# ArduinoUno.net
KiCad netlist of a schematic drawn in Altium Designer
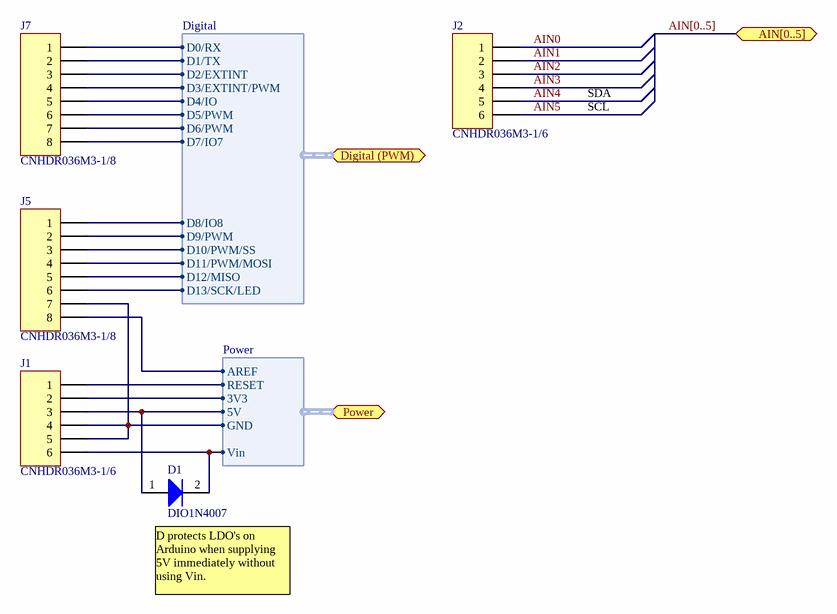
[diagram p0: ArduinoUno.SchDoc]

(export (version "E")
  (design (tool "Eeschema 10.0.6"))
  (components
    (comp (ref "D1")
      (value "DIO1N4007")
      (footprint "DO-41")
      (description "1 Amp General Purpose Rectifier")
      (libsource (lib "Testing") (part "D_DIODE"))
    )
    (comp (ref "J1")
      (value "CNHDR036M3-1/6")
      (footprint "J_HDR1X6")
      (libsource (lib "Testing") (part "J_6P"))
    )
    (comp (ref "J2")
      (value "CNHDR036M3-1/6")
      (footprint "J_HDR1X6")
      (libsource (lib "Testing") (part "J_6P"))
    )
    (comp (ref "J5")
      (value "CNHDR036M3-1/8")
      (footprint "J_HDR1X8")
      (libsource (lib "Testing") (part "J_8P"))
    )
    (comp (ref "J7")
      (value "CNHDR036M3-1/8")
      (footprint "J_HDR1X8")
      (libsource (lib "Testing") (part "J_8P"))
    )
  )
  (nets
    (net (code "3") (name "/3V3") (class "Default")
      (node (ref "J1") (pin "2") (pinfunction "2_2") (pintype "passive"))
    )
    (net (code "4") (name "/5V") (class "Default")
      (node (ref "D1") (pin "1") (pinfunction "A_1") (pintype "passive"))
      (node (ref "J1") (pin "3") (pinfunction "3_3") (pintype "passive"))
    )
    (net (code "5") (name "/AIN0") (class "Default")
      (node (ref "J2") (pin "1") (pinfunction "1_1") (pintype "passive"))
    )
    (net (code "6") (name "/AIN1") (class "Default")
      (node (ref "J2") (pin "2") (pinfunction "2_2") (pintype "passive"))
    )
    (net (code "7") (name "/AIN2") (class "Default")
      (node (ref "J2") (pin "3") (pinfunction "3_3") (pintype "passive"))
    )
    (net (code "8") (name "/AIN3") (class "Default")
      (node (ref "J2") (pin "4") (pinfunction "4_4") (pintype "passive"))
    )
    (net (code "9") (name "/AIN4") (class "Default")
      (node (ref "J2") (pin "5") (pinfunction "5_5") (pintype "passive"))
    )
    (net (code "10") (name "/AIN5") (class "Default")
      (node (ref "J2") (pin "6") (pinfunction "6_6") (pintype "passive"))
    )
    (net (code "12") (name "/AREF") (class "Default")
      (node (ref "J5") (pin "8") (pinfunction "8_8") (pintype "passive"))
    )
    (net (code "13") (name "/D0{slash}RX") (class "Default")
      (node (ref "J7") (pin "1") (pinfunction "1_1") (pintype "passive"))
    )
    (net (code "14") (name "/D1{slash}TX") (class "Default")
      (node (ref "J7") (pin "2") (pinfunction "2_2") (pintype "passive"))
    )
    (net (code "15") (name "/D2{slash}EXTINT") (class "Default")
      (node (ref "J7") (pin "3") (pinfunction "3_3") (pintype "passive"))
    )
    (net (code "16") (name "/D3{slash}EXTINT{slash}PWM") (class "Default")
      (node (ref "J7") (pin "4") (pinfunction "4_4") (pintype "passive"))
    )
    (net (code "17") (name "/D4{slash}IO") (class "Default")
      (node (ref "J7") (pin "5") (pinfunction "5_5") (pintype "passive"))
    )
    (net (code "18") (name "/D5{slash}PWM") (class "Default")
      (node (ref "J7") (pin "6") (pinfunction "6_6") (pintype "passive"))
    )
    (net (code "19") (name "/D6{slash}PWM") (class "Default")
      (node (ref "J7") (pin "7") (pinfunction "7_7") (pintype "passive"))
    )
    (net (code "20") (name "/D7{slash}IO7") (class "Default")
      (node (ref "J7") (pin "8") (pinfunction "8_8") (pintype "passive"))
    )
    (net (code "21") (name "/D8{slash}IO8") (class "Default")
      (node (ref "J5") (pin "1") (pinfunction "1_1") (pintype "passive"))
    )
    (net (code "22") (name "/D9{slash}PWM") (class "Default")
      (node (ref "J5") (pin "2") (pinfunction "2_2") (pintype "passive"))
    )
    (net (code "23") (name "/D10{slash}PWM{slash}SS") (class "Default")
      (node (ref "J5") (pin "3") (pinfunction "3_3") (pintype "passive"))
    )
    (net (code "24") (name "/D11{slash}PWM{slash}MOSI") (class "Default")
      (node (ref "J5") (pin "4") (pinfunction "4_4") (pintype "passive"))
    )
    (net (code "25") (name "/D12{slash}MISO") (class "Default")
      (node (ref "J5") (pin "5") (pinfunction "5_5") (pintype "passive"))
    )
    (net (code "26") (name "/D13{slash}SCK{slash}LED") (class "Default")
      (node (ref "J5") (pin "6") (pinfunction "6_6") (pintype "passive"))
    )
    (net (code "27") (name "/GND") (class "Default")
      (node (ref "J1") (pin "4") (pinfunction "4_4") (pintype "passive"))
      (node (ref "J1") (pin "5") (pinfunction "5_5") (pintype "passive"))
      (node (ref "J5") (pin "7") (pinfunction "7_7") (pintype "passive"))
    )
    (net (code "28") (name "/RESET") (class "Default")
      (node (ref "J1") (pin "1") (pinfunction "1_1") (pintype "passive"))
    )
    (net (code "29") (name "/Vin") (class "Default")
      (node (ref "D1") (pin "2") (pinfunction "K_2") (pintype "passive"))
      (node (ref "J1") (pin "6") (pinfunction "6_6") (pintype "passive"))
    )
  )
)
